# 15_CAN_BUS.net
KiCad netlist of a schematic drawn in Altium Designer
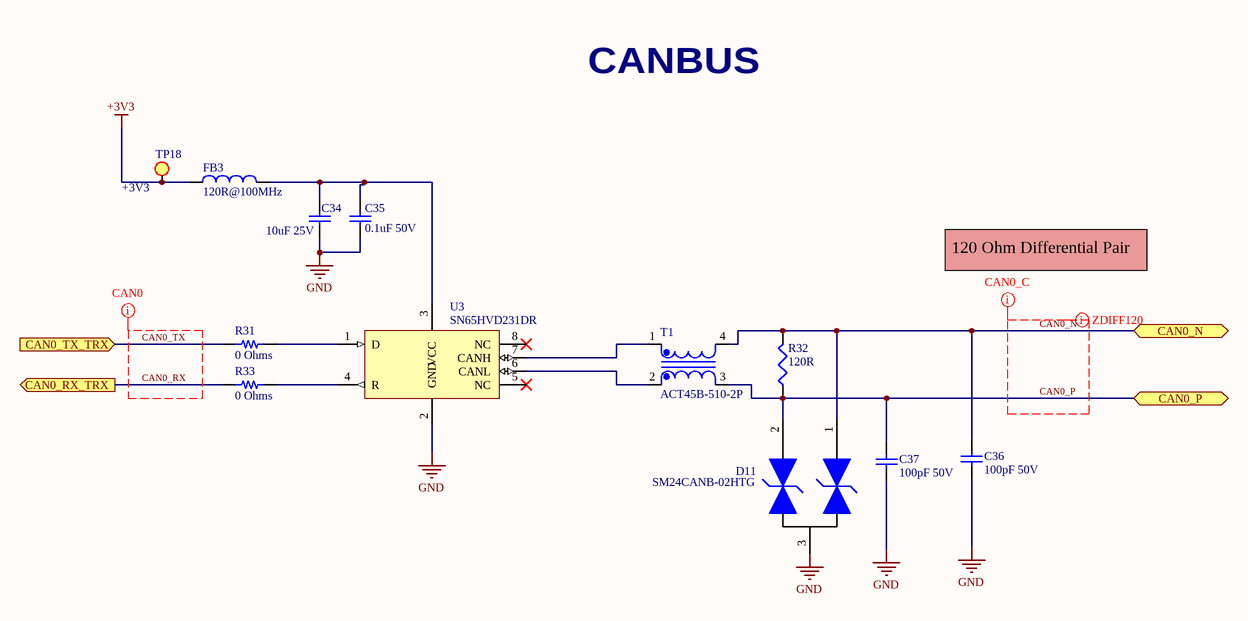
[diagram p0: 15_CAN_BUS.SchDoc]

(export (version "E")
  (design (tool "Eeschema 10.0.6"))
  (components
    (comp (ref "C34")
      (value "10uF 25V")
      (footprint "SMC0805")
      (description "10 µF ±10% 25V Ceramic Capacitor X5R 0805 (2012 Metric)")
      (fields
        (field (name "MANUFACTURER PART NUMBER") "CL21A106KAYNNNE")
        (field (name "LCSC PART NUMBER") "C15850")
      )
      (libsource (lib "HW_HOLLAND_NCDM_MONITOR_R1") (part "CAP0805_10UF_25V"))
    )
    (comp (ref "C35")
      (value "0.1uF 50V")
      (footprint "SMC0603")
      (description "0.1 µF ±10% 50V Ceramic Capacitor X7R 0603 (1608 Metric)")
      (fields
        (field (name "MANUFACTURER PART NUMBER") "CL10B104KB8NNNL")
        (field (name "LCSC PART NUMBER") "C1591")
      )
      (libsource (lib "HW_HOLLAND_NCDM_MONITOR_R1") (part "CAP0603_0.1UF_50V"))
    )
    (comp (ref "C36")
      (value "100pF 50V")
      (footprint "SMC0603")
      (description "100 pF ±5% 50V Ceramic Capacitor C0G, NP0 0603 (1608 Metric)")
      (fields
        (field (name "MANUFACTURER PART NUMBER") "06035A101JAT2A")
        (field (name "LCSC PART NUMBER") "C14665")
      )
      (libsource (lib "HW_HOLLAND_NCDM_MONITOR_R1") (part "CAP0603_100PF_50V"))
    )
    (comp (ref "C37")
      (value "100pF 50V")
      (footprint "SMC0603")
      (description "100 pF ±5% 50V Ceramic Capacitor C0G, NP0 0603 (1608 Metric)")
      (fields
        (field (name "MANUFACTURER PART NUMBER") "06035A101JAT2A")
        (field (name "LCSC PART NUMBER") "C14665")
      )
      (libsource (lib "HW_HOLLAND_NCDM_MONITOR_R1") (part "CAP0603_100PF_50V"))
    )
    (comp (ref "D11")
      (value "CAN")
      (footprint "SOT23_3-DIODE")
      (description "TVS DIODE 24VWM 50VC SOT23-3")
      (fields
        (field (name "LCSC MANUFACTURER PART NUMBER") "SM24CANB-02HTG")
        (field (name "LCSC PART NUMBER") "C151237")
        (field (name "MANUFACTURER PART NUMBER") "SM24CANB-02HTG")
      )
      (libsource (lib "HW_HOLLAND_NCDM_MONITOR_R1") (part "SM24CANB-02HTG_TVS"))
    )
    (comp (ref "FB3")
      (value "120R@100MHz")
      (footprint "FB 0603(1608)")
      (description "120 Ohms @ 100 MHz 1 Power Line Ferrite Bead 0603 (1608 Metric) 3A 30mOhm")
      (fields
        (field (name "MANUFACTURER PART NUMBER") "BLM18KG121TH1D")
        (field (name "LCSC PART NUMBER") "C437404")
      )
      (libsource (lib "HW_HOLLAND_NCDM_MONITOR_R1") (part "FB0603_120R@100MHz"))
    )
    (comp (ref "R31")
      (value "0 Ohms")
      (footprint "RES 0402_1005")
      (description "RES 0 OHM JUMPER 1/8W 0402")
      (fields
        (field (name "PART NUMBER") "HCJ0402ZT0R00")
        (field (name "MANUFACTURER") "Stackpole Electronics Inc")
      )
      (libsource (lib "Celestial Altium Library - altium_library") (part "Resistor"))
    )
    (comp (ref "R32")
      (value "120R")
      (footprint "RES1206")
      (fields
        (field (name "MANUFACTURER PART NUMBER") "AC1206FR-07120RL")
        (field (name "LCSC PART NUMBER") "C229293")
        (field (name "Comment") "RES SMD 120 OHM 1% 1/4W 1206")
      )
      (libsource (lib "HW_HOLLAND_NCDM_MONITOR_R1") (part "RES1206_120R_%1"))
    )
    (comp (ref "R33")
      (value "0 Ohms")
      (footprint "RES 0402_1005")
      (description "RES 0 OHM JUMPER 1/8W 0402")
      (fields
        (field (name "PART NUMBER") "HCJ0402ZT0R00")
        (field (name "MANUFACTURER") "Stackpole Electronics Inc")
      )
      (libsource (lib "Celestial Altium Library - altium_library") (part "Resistor"))
    )
    (comp (ref "T1")
      (value "ACT45B-510-2P")
      (footprint "TDK_ACT45B-510-2P-TL003_0")
      (description "Ind Common Mode Filter Wirewound 51uH 2KOhm -30% to 50% 100KHz 200mA 1812 T/R")
      (fields
        (field (name "MANUFACTURER") "TDK")
        (field (name "MANUFACTURER PART NUMBER") "ACT45B-510-2P-TL003")
      )
      (libsource (lib "HW_HOLLAND_NCDM_MONITOR_R1") (part "ACT45B-510-2P"))
    )
    (comp (ref "TP18")
      (value "+3V3")
      (footprint "TEST_POINT")
      (libsource (lib "HW_HOLLAND_NCDM_MONITOR_R1") (part "TP_1"))
    )
    (comp (ref "U3")
      (value "IC TRANSCEIVER HALF 1/1 8SOIC")
      (footprint "SOIC8 - duplicate")
      (description "1/1 Transceiver Half CANbus 8-SOIC")
      (fields
        (field (name "LCSC MANUFACTURER PART NUMBER") "SN65HVD231DR")
        (field (name "LCSC PART NUMBER") "C129257")
        (field (name "P/N") "SN65HVD231DR")
      )
      (libsource (lib "HW_HOLLAND_NCDM_MONITOR_R1") (part "SN65HVD231DR"))
    )
  )
  (nets
    (net (code "1") (name "+3V3") (class "Default")
      (node (ref "FB3") (pin "1") (pinfunction "1_1") (pintype "passive"))
      (node (ref "TP18") (pin "1") (pinfunction "TP_1") (pintype "passive"))
    )
    (net (code "2") (name "/CAN0_N") (class "Default")
      (node (ref "C36") (pin "2") (pinfunction "2_2") (pintype "passive"))
      (node (ref "D11") (pin "1") (pinfunction "1_1") (pintype "passive"))
      (node (ref "R32") (pin "2") (pinfunction "2_2") (pintype "passive"))
      (node (ref "T1") (pin "4") (pinfunction "4_4") (pintype "passive"))
    )
    (net (code "3") (name "/CAN0_P") (class "Default")
      (node (ref "C37") (pin "2") (pinfunction "2_2") (pintype "passive"))
      (node (ref "D11") (pin "2") (pinfunction "2_2") (pintype "passive"))
      (node (ref "R32") (pin "1") (pinfunction "1_1") (pintype "passive"))
      (node (ref "T1") (pin "3") (pinfunction "3_3") (pintype "passive"))
    )
    (net (code "4") (name "/CAN0_RX") (class "Default")
      (node (ref "R33") (pin "2") (pinfunction "2_2") (pintype "passive"))
    )
    (net (code "5") (name "/CAN0_TX") (class "Default")
      (node (ref "R31") (pin "2") (pinfunction "2_2") (pintype "passive"))
    )
    (net (code "6") (name "GND") (class "Default")
      (node (ref "C34") (pin "1") (pinfunction "1_1") (pintype "passive"))
      (node (ref "C35") (pin "1") (pinfunction "1_1") (pintype "passive"))
      (node (ref "C36") (pin "1") (pinfunction "1_1") (pintype "passive"))
      (node (ref "C37") (pin "1") (pinfunction "1_1") (pintype "passive"))
      (node (ref "D11") (pin "3") (pinfunction "3_3") (pintype "passive"))
      (node (ref "U3") (pin "2") (pinfunction "GND_2") (pintype "passive"))
    )
    (net (code "7") (name "Net-(U3-CANH)") (class "Default")
      (node (ref "T1") (pin "1") (pinfunction "1_1") (pintype "passive"))
      (node (ref "U3") (pin "7") (pinfunction "CANH_7") (pintype "bidirectional"))
    )
    (net (code "8") (name "Net-(U3-CANL)") (class "Default")
      (node (ref "T1") (pin "2") (pinfunction "2_2") (pintype "passive"))
      (node (ref "U3") (pin "6") (pinfunction "CANL_6") (pintype "bidirectional"))
    )
    (net (code "9") (name "Net-(U3-D)") (class "Default")
      (node (ref "R31") (pin "1") (pinfunction "1_1") (pintype "passive"))
      (node (ref "U3") (pin "1") (pinfunction "D_1") (pintype "input"))
    )
    (net (code "10") (name "Net-(U3-R)") (class "Default")
      (node (ref "R33") (pin "1") (pinfunction "1_1") (pintype "passive"))
      (node (ref "U3") (pin "4") (pinfunction "R_4") (pintype "output"))
    )
    (net (code "11") (name "Net-(U3-VCC)") (class "Default")
      (node (ref "C34") (pin "2") (pinfunction "2_2") (pintype "passive"))
      (node (ref "C35") (pin "2") (pinfunction "2_2") (pintype "passive"))
      (node (ref "FB3") (pin "2") (pinfunction "2_2") (pintype "passive"))
      (node (ref "U3") (pin "3") (pinfunction "VCC_3") (pintype "passive"))
    )
    (net (code "12") (name "unconnected-(U3-NC-Pad5)") (class "Default")
      (node (ref "U3") (pin "5") (pinfunction "NC_5") (pintype "passive+no_connect"))
    )
    (net (code "13") (name "unconnected-(U3-NC-Pad8)") (class "Default")
      (node (ref "U3") (pin "8") (pinfunction "NC_8") (pintype "passive+no_connect"))
    )
  )
)
